# Becca_Sap_Flow_Power_Board.net
KiCad netlist of a schematic drawn in EAGLE
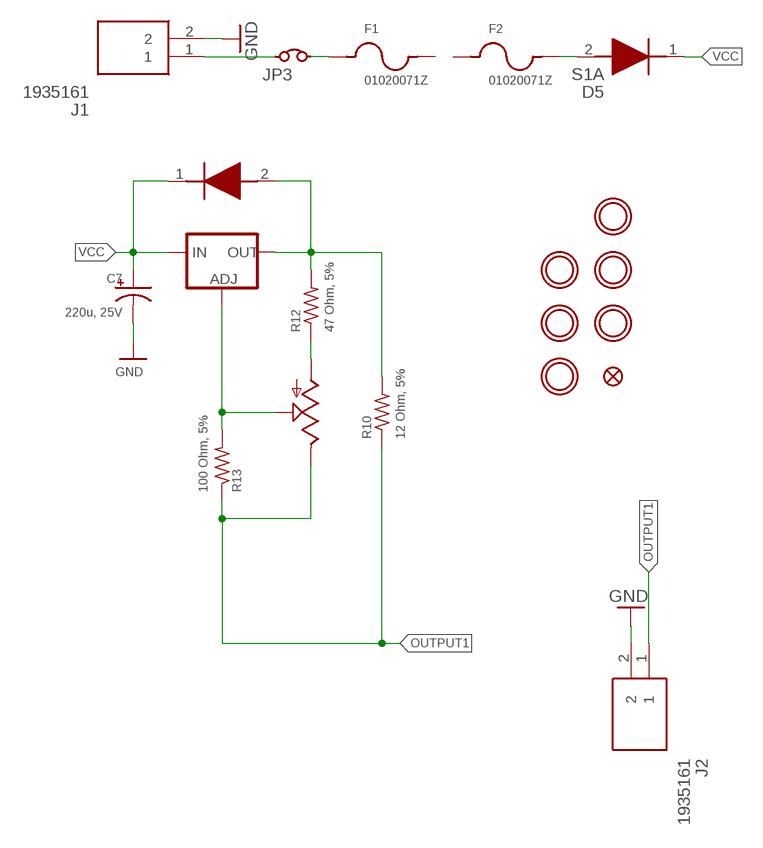
[diagram p0: schematic, sheet 1]

(export (version "E")
  (design (tool "Eeschema 10.0.6"))
  (components
    (comp (ref "C7")
      (value "220u, 25V")
      (footprint "eagle-import:PANASONIC_C")
      (libsource (lib "eagle-import") (part "CPOL-USC"))
    )
    (comp (ref "D5")
      (value "S1A")
      (footprint "eagle-import:DIOM5027X250N")
      (fields (field (name "MOUSER_PART_NUMBER") "637-S1A"))
      (libsource (lib "eagle-import") (part "S1A"))
    )
    (comp (ref "D6")
      (value "S1A")
      (footprint "eagle-import:DIOM5027X250N")
      (fields (field (name "MOUSER_PART_NUMBER") "637-S1A"))
      (libsource (lib "eagle-import") (part "S1A"))
    )
    (comp (ref "F1")
      (value "01020071Z")
      (footprint "eagle-import:01020071Z")
      (fields (field (name "MANUFACTURER") "Littelfuse Inc.") (field (name "CREATED_BY") "PCBLayout.com"))
      (libsource (lib "eagle-import") (part "01020071Z"))
    )
    (comp (ref "F2")
      (value "01020071Z")
      (footprint "eagle-import:01020071Z")
      (fields (field (name "MANUFACTURER") "Littelfuse Inc.") (field (name "CREATED_BY") "PCBLayout.com"))
      (libsource (lib "eagle-import") (part "01020071Z"))
    )
    (comp (ref "FID2")
      (value "FIDUCIAL_1MM")
      (footprint "eagle-import:FIDUCIAL_1MM")
      (libsource (lib "eagle-import") (part "FIDUCIAL_1MM"))
    )
    (comp (ref "J1")
      (value "1935161")
      (footprint "eagle-import:1935161")
      (fields (field (name "MOUSER_PART_NUMBER") "651-1935161"))
      (libsource (lib "eagle-import") (part "1935161"))
    )
    (comp (ref "J2")
      (value "1935161")
      (footprint "eagle-import:1935161")
      (fields (field (name "MOUSER_PART_NUMBER") "651-1935161"))
      (libsource (lib "eagle-import") (part "1935161"))
    )
    (comp (ref "JP3")
      (value "JUMPER")
      (footprint "eagle-import:HDR2X1")
      (libsource (lib "eagle-import") (part "JUMPER"))
    )
    (comp (ref "R10")
      (value "12 Ohm, 5%")
      (footprint "eagle-import:R0805")
      (libsource (lib "eagle-import") (part "R-US_R0805"))
    )
    (comp (ref "R12")
      (value "47 Ohm, 5%")
      (footprint "eagle-import:R0805")
      (libsource (lib "eagle-import") (part "R-US_R0805"))
    )
    (comp (ref "R13")
      (value "100 Ohm, 5%")
      (footprint "eagle-import:R0805")
      (libsource (lib "eagle-import") (part "R-US_R0805"))
    )
    (comp (ref "U$1")
      (value "MOUNTINGHOLE2.5")
      (footprint "eagle-import:MOUNTINGHOLE_2.5_PLATED")
      (libsource (lib "eagle-import") (part "MOUNTINGHOLE2.5"))
    )
    (comp (ref "U$2")
      (value "MOUNTINGHOLE2.5")
      (footprint "eagle-import:MOUNTINGHOLE_2.5_PLATED")
      (libsource (lib "eagle-import") (part "MOUNTINGHOLE2.5"))
    )
    (comp (ref "U$3")
      (value "MOUNTINGHOLE2.5")
      (footprint "eagle-import:MOUNTINGHOLE_2.5_PLATED")
      (libsource (lib "eagle-import") (part "MOUNTINGHOLE2.5"))
    )
    (comp (ref "U$4")
      (value "MOUNTINGHOLE2.5")
      (footprint "eagle-import:MOUNTINGHOLE_2.5_PLATED")
      (libsource (lib "eagle-import") (part "MOUNTINGHOLE2.5"))
    )
    (comp (ref "U$5")
      (value "MOUNTINGHOLE2.5")
      (footprint "eagle-import:MOUNTINGHOLE_2.5_PLATED")
      (libsource (lib "eagle-import") (part "MOUNTINGHOLE2.5"))
    )
    (comp (ref "U$11")
      (value "MOUNTINGHOLE2.5")
      (footprint "eagle-import:MOUNTINGHOLE_2.5_PLATED")
      (libsource (lib "eagle-import") (part "MOUNTINGHOLE2.5"))
    )
    (comp (ref "U1")
      (value "V_REG_317SMD")
      (footprint "eagle-import:SOT223")
      (libsource (lib "eagle-import") (part "V_REG_317SMD"))
    )
    (comp (ref "VR1")
      (value "3296W-1-102RLF")
      (footprint "eagle-import:3296W1102RLF")
      (fields (field (name "MOUSER_PART_NUMBER") "652-3296W-1-102RLF"))
      (libsource (lib "eagle-import") (part "3296W-1-102RLF"))
    )
  )
  (nets
    (net (code "1") (name "GND") (class "Default")
      (node (ref "C7") (pin "-") (pinfunction "-_-") (pintype "passive"))
      (node (ref "J1") (pin "2") (pinfunction "2_2") (pintype "bidirectional"))
      (node (ref "J2") (pin "2") (pinfunction "2_2") (pintype "bidirectional"))
    )
    (net (code "2") (name "Net-(D5-A)") (class "Default")
      (node (ref "D5") (pin "2") (pinfunction "A_2") (pintype "bidirectional"))
      (node (ref "F2") (pin "2") (pinfunction "2_2") (pintype "passive"))
    )
    (net (code "3") (name "Net-(D6-A)") (class "Default")
      (node (ref "D6") (pin "2") (pinfunction "A_2") (pintype "bidirectional"))
      (node (ref "R10") (pin "2") (pinfunction "2_2") (pintype "passive"))
      (node (ref "R12") (pin "2") (pinfunction "2_2") (pintype "passive"))
      (node (ref "U1") (pin "2") (pinfunction "OUT_2") (pintype "output"))
    )
    (net (code "4") (name "Net-(F1-Pad1)") (class "Default")
      (node (ref "F1") (pin "1") (pinfunction "1_1") (pintype "passive"))
      (node (ref "JP3") (pin "2") (pinfunction "2_2") (pintype "passive"))
    )
    (net (code "5") (name "Net-(J1-Pad1)") (class "Default")
      (node (ref "J1") (pin "1") (pinfunction "1_1") (pintype "bidirectional"))
      (node (ref "JP3") (pin "1") (pinfunction "1_1") (pintype "passive"))
    )
    (net (code "6") (name "Net-(U1-ADJ)") (class "Default")
      (node (ref "R13") (pin "2") (pinfunction "2_2") (pintype "passive"))
      (node (ref "U1") (pin "1") (pinfunction "ADJ_1") (pintype "input"))
      (node (ref "VR1") (pin "2") (pinfunction "S_2") (pintype "passive"))
    )
    (net (code "7") (name "Net-(VR1-A)") (class "Default")
      (node (ref "R12") (pin "1") (pinfunction "1_1") (pintype "passive"))
      (node (ref "VR1") (pin "1") (pinfunction "A_1") (pintype "passive"))
    )
    (net (code "8") (name "OUTPUT1") (class "Default")
      (node (ref "J2") (pin "1") (pinfunction "1_1") (pintype "bidirectional"))
      (node (ref "R10") (pin "1") (pinfunction "1_1") (pintype "passive"))
      (node (ref "R13") (pin "1") (pinfunction "1_1") (pintype "passive"))
      (node (ref "VR1") (pin "3") (pinfunction "E_3") (pintype "passive"))
    )
    (net (code "9") (name "VCC") (class "Default")
      (node (ref "C7") (pin "+") (pinfunction "+_+") (pintype "passive"))
      (node (ref "D5") (pin "1") (pinfunction "K_1") (pintype "bidirectional"))
      (node (ref "D6") (pin "1") (pinfunction "K_1") (pintype "bidirectional"))
      (node (ref "U1") (pin "3") (pinfunction "IN_3") (pintype "input"))
    )
    (net (code "10") (name "unconnected-(F1-Pad2)") (class "Default")
      (node (ref "F1") (pin "2") (pinfunction "2_2") (pintype "passive"))
    )
    (net (code "11") (name "unconnected-(F2-Pad1)") (class "Default")
      (node (ref "F2") (pin "1") (pinfunction "1_1") (pintype "passive"))
    )
  )
)
